# CNC-PowerSwitch-2016-v0_92.net
KiCad netlist of a schematic drawn in EAGLE
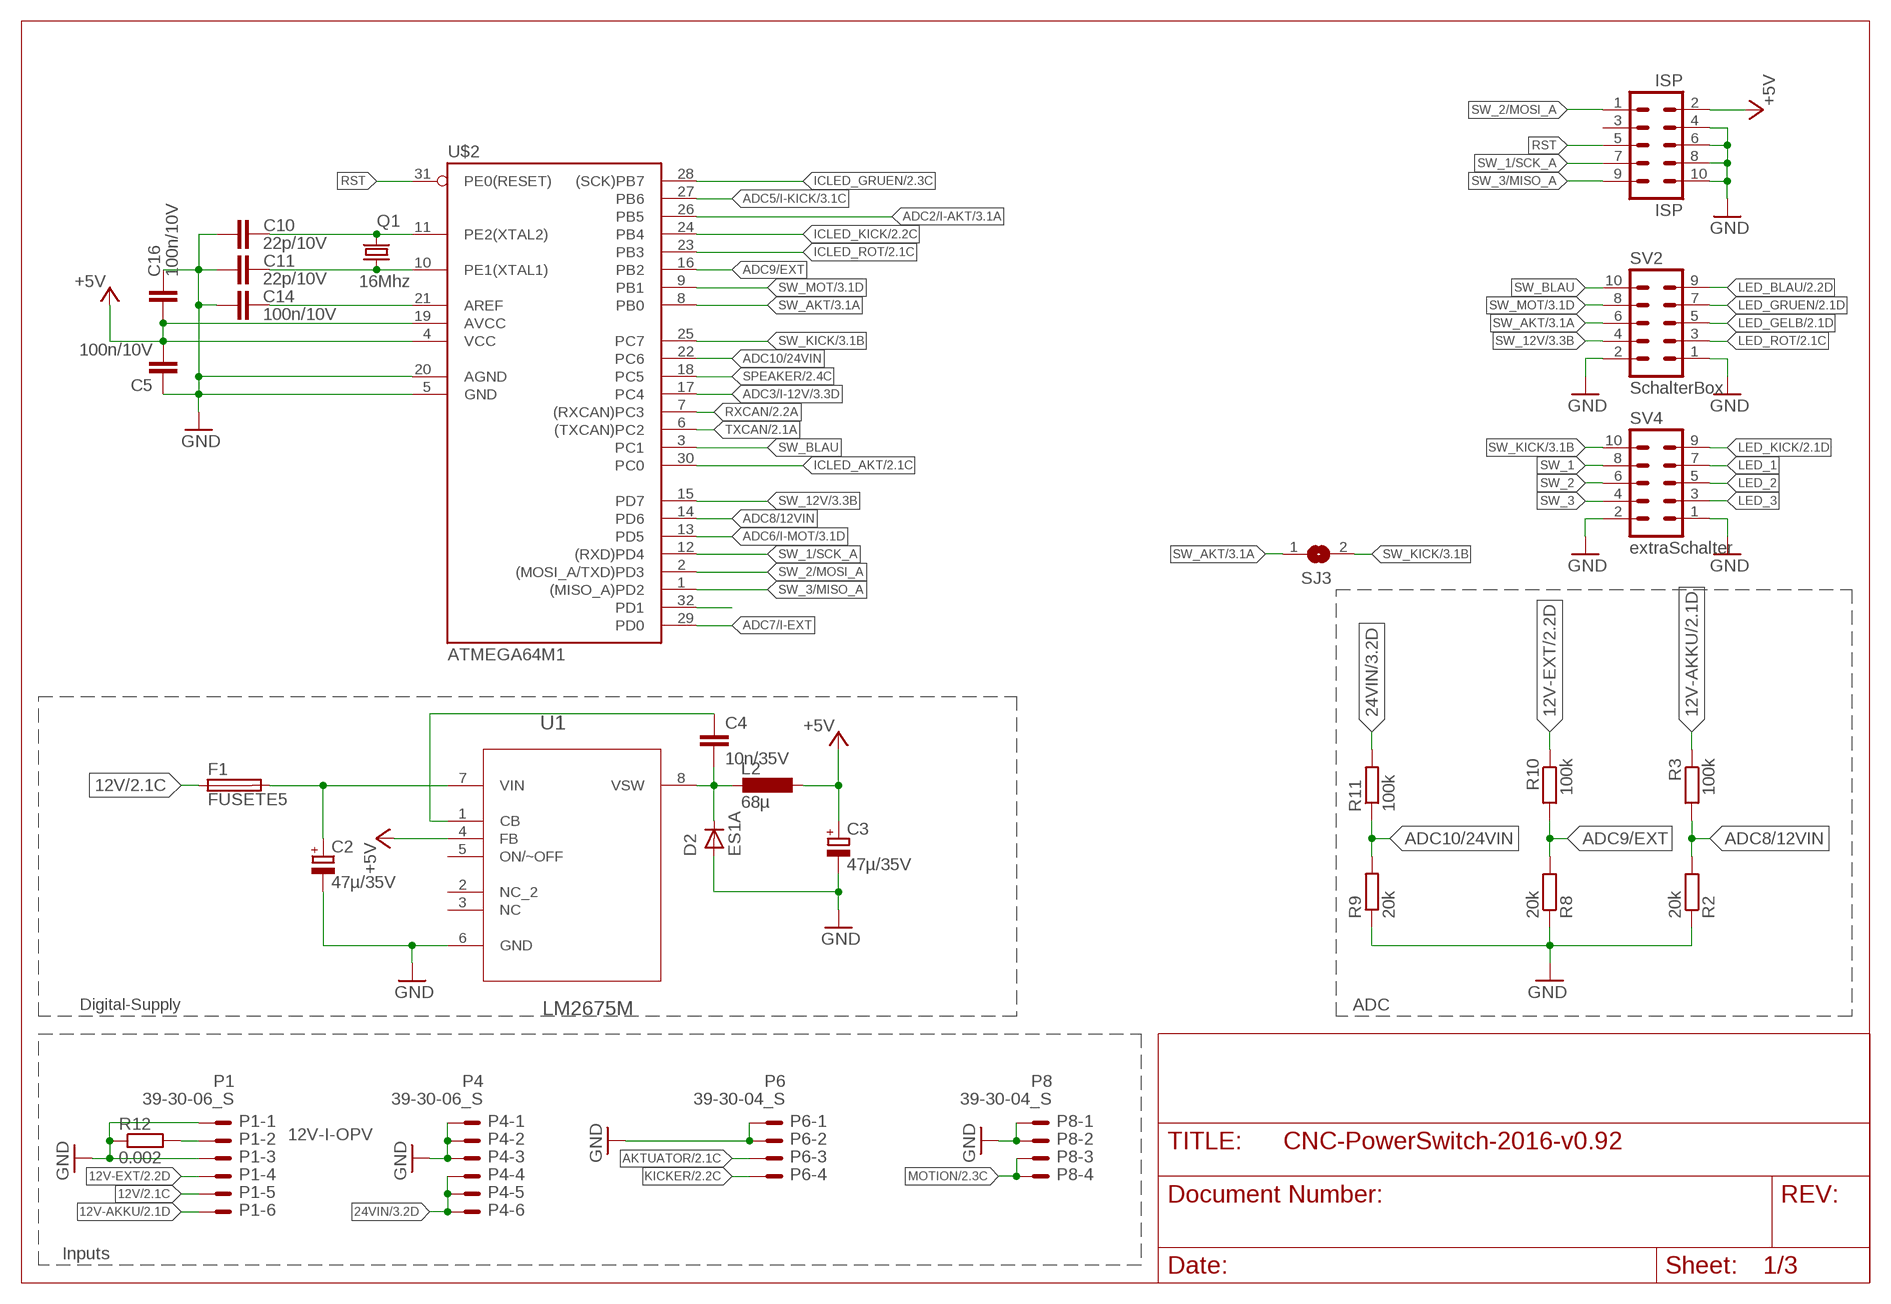
[diagram p0: schematic, sheet 1]
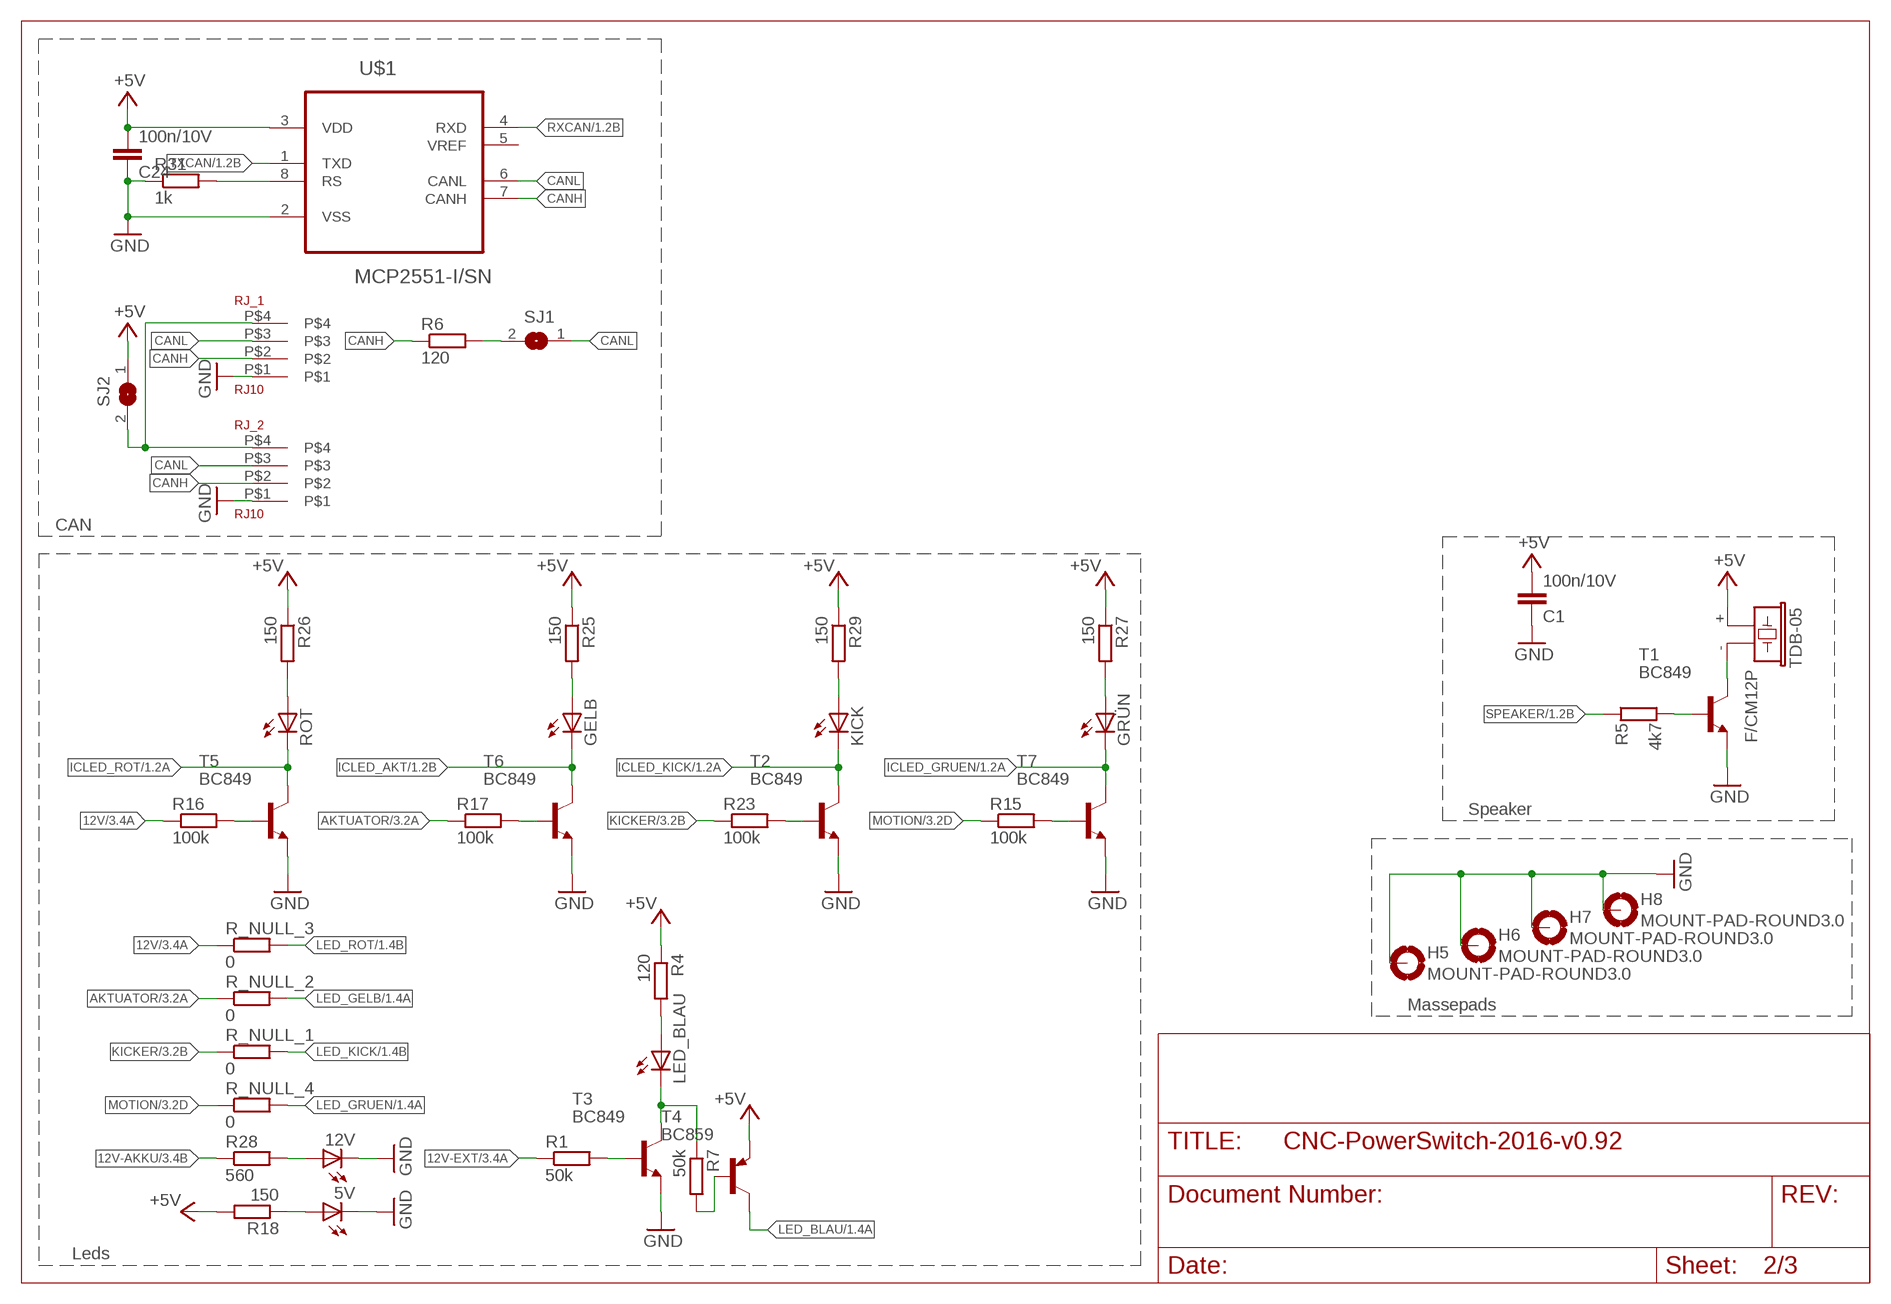
[diagram p1: schematic, sheet 2]
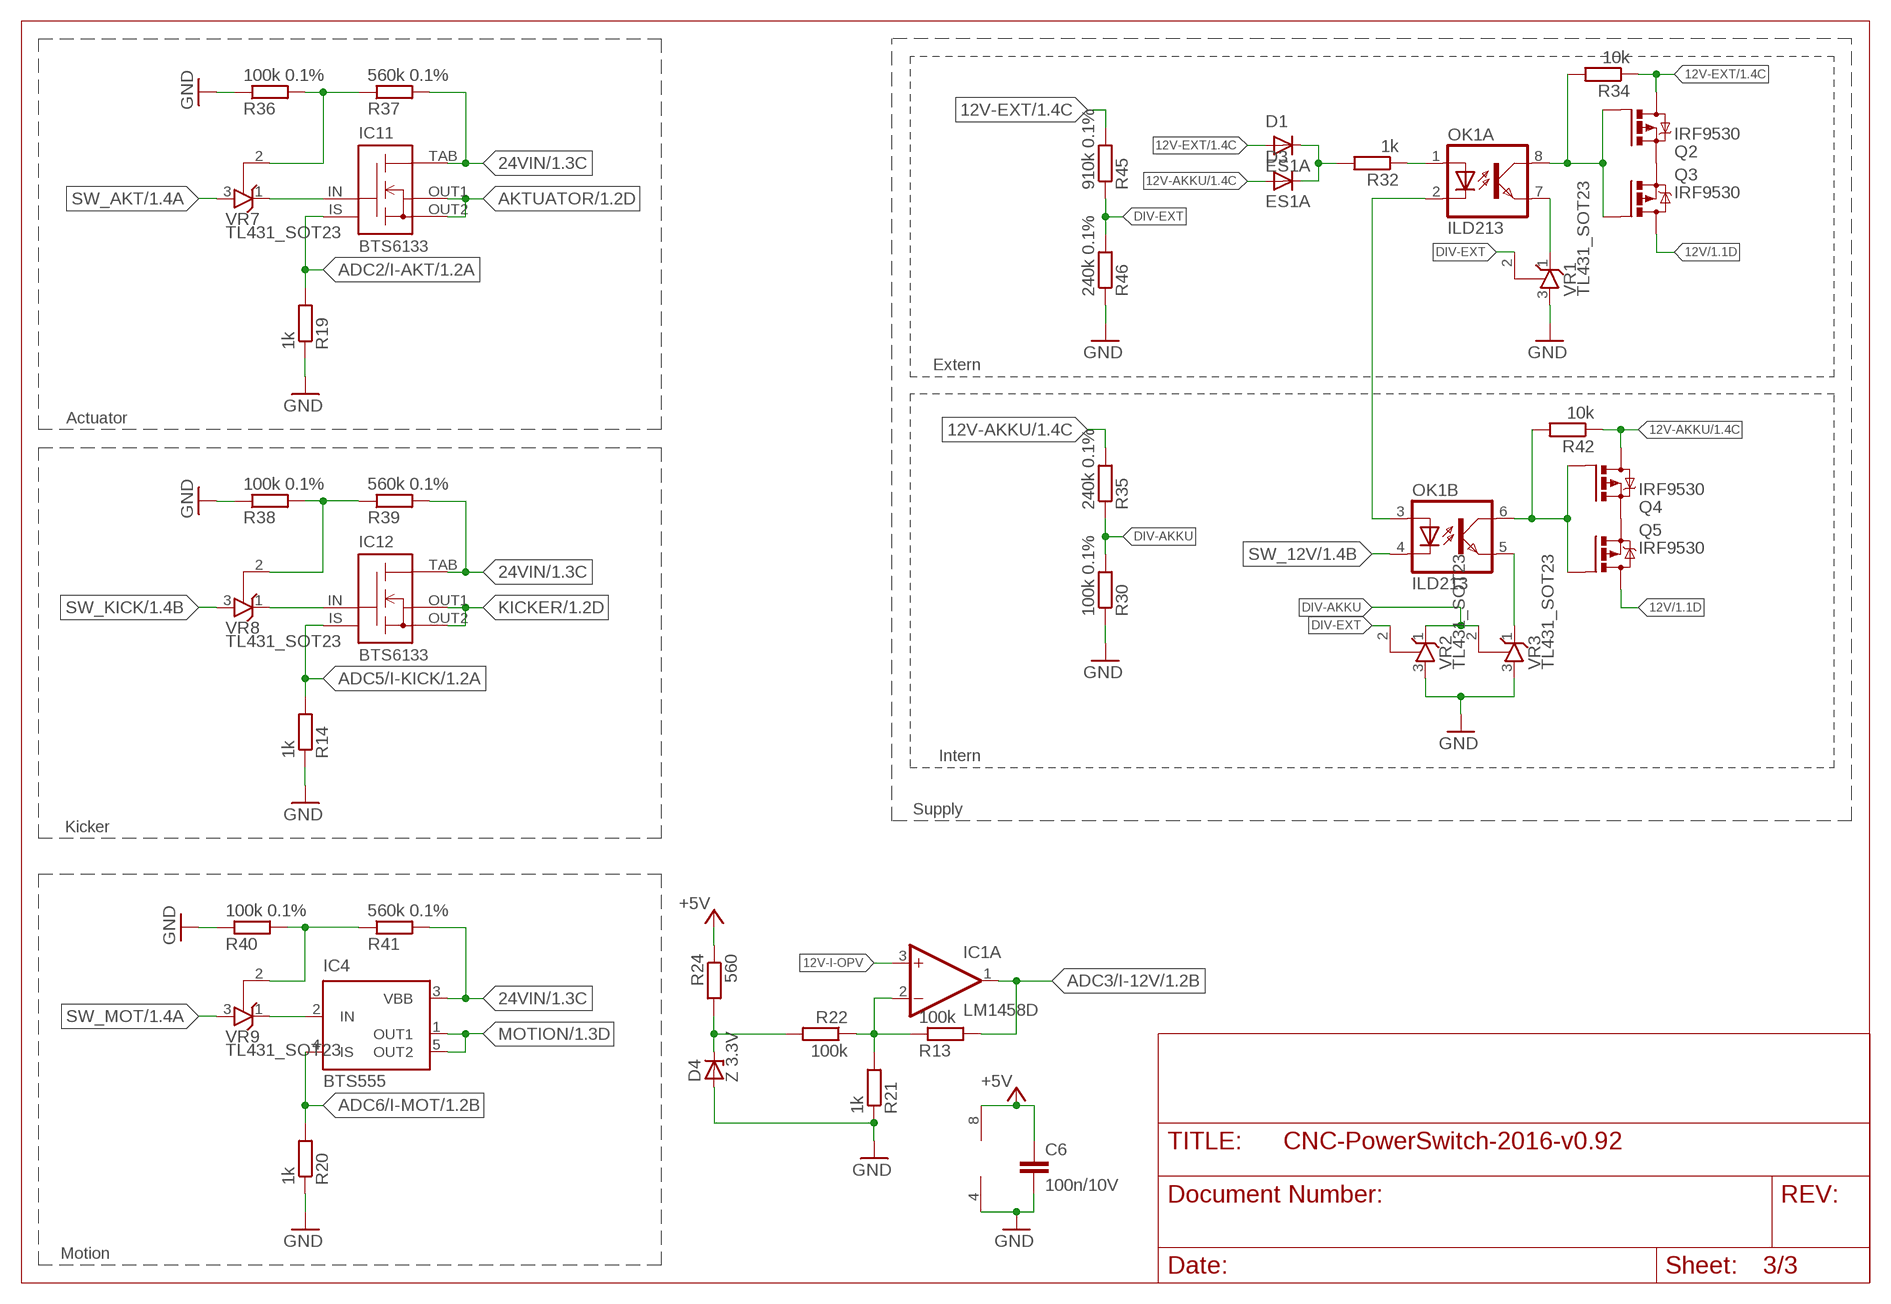
[diagram p2: schematic, sheet 3]

(export (version "E")
  (design (tool "Eeschema 10.0.6"))
  (components
    (comp (ref "C6")
      (value "100n/10V")
      (footprint "eagle-import:C0603")
      (libsource (lib "eagle-import") (part "C-EUC0603"))
    )
    (comp (ref "D1")
      (value "ES1A")
      (footprint "eagle-import:SMA-DO214AC")
      (libsource (lib "eagle-import") (part "GF1"))
    )
    (comp (ref "D3")
      (value "ES1A")
      (footprint "eagle-import:SMA-DO214AC")
      (libsource (lib "eagle-import") (part "GF1"))
    )
    (comp (ref "D4")
      (value "Z 3.3V")
      (footprint "eagle-import:SOT23")
      (libsource (lib "eagle-import") (part "ZENER-DIODESOT23"))
    )
    (comp (ref "IC1")
      (value "LM1458D")
      (footprint "eagle-import:SO08")
      (libsource (lib "eagle-import") (part "1458DLM"))
    )
    (comp (ref "IC4")
      (value "BTS555")
      (footprint "eagle-import:TO220-51")
      (fields (field (name "MF") "FARNELL") (field (name "MPN") "BTS555."))
      (libsource (lib "eagle-import") (part "BTS555"))
    )
    (comp (ref "IC11")
      (value "BTS6133")
      (footprint "eagle-import:TO252-51")
      (libsource (lib "eagle-import") (part "BTS6133"))
    )
    (comp (ref "IC12")
      (value "BTS6133")
      (footprint "eagle-import:TO252-51")
      (libsource (lib "eagle-import") (part "BTS6133"))
    )
    (comp (ref "OK1")
      (value "ILD213")
      (footprint "eagle-import:SOIC08")
      (fields (field (name "MF") "VISHAY/TELEFUNKEN") (field (name "MPN") "ILD213T"))
      (libsource (lib "eagle-import") (part "ILD213"))
    )
    (comp (ref "Q2")
      (value "IRF9530")
      (footprint "eagle-import:TO220BV")
      (libsource (lib "eagle-import") (part "IRF9530"))
    )
    (comp (ref "Q3")
      (value "IRF9530")
      (footprint "eagle-import:TO220BV")
      (libsource (lib "eagle-import") (part "IRF9530"))
    )
    (comp (ref "Q4")
      (value "IRF9530")
      (footprint "eagle-import:TO220BV")
      (libsource (lib "eagle-import") (part "IRF9530"))
    )
    (comp (ref "Q5")
      (value "IRF9530")
      (footprint "eagle-import:TO220BV")
      (libsource (lib "eagle-import") (part "IRF9530"))
    )
    (comp (ref "R13")
      (value "100k")
      (footprint "eagle-import:R0805")
      (libsource (lib "eagle-import") (part "R-EU_R0805"))
    )
    (comp (ref "R14")
      (value "1k")
      (footprint "eagle-import:R0805")
      (libsource (lib "eagle-import") (part "R-EU_R0805"))
    )
    (comp (ref "R19")
      (value "1k")
      (footprint "eagle-import:R0805")
      (libsource (lib "eagle-import") (part "R-EU_R0805"))
    )
    (comp (ref "R20")
      (value "1k")
      (footprint "eagle-import:R0805")
      (libsource (lib "eagle-import") (part "R-EU_R0805"))
    )
    (comp (ref "R21")
      (value "1k")
      (footprint "eagle-import:R0805")
      (libsource (lib "eagle-import") (part "R-EU_R0805"))
    )
    (comp (ref "R22")
      (value "100k")
      (footprint "eagle-import:R0805")
      (libsource (lib "eagle-import") (part "R-EU_R0805"))
    )
    (comp (ref "R24")
      (value "560")
      (footprint "eagle-import:R0805")
      (libsource (lib "eagle-import") (part "R-EU_R0805"))
    )
    (comp (ref "R30")
      (value "100k 0.1%")
      (footprint "eagle-import:R0805")
      (libsource (lib "eagle-import") (part "R-EU_R0805"))
    )
    (comp (ref "R32")
      (value "1k")
      (footprint "eagle-import:R0805")
      (libsource (lib "eagle-import") (part "R-EU_R0805"))
    )
    (comp (ref "R34")
      (value "10k")
      (footprint "eagle-import:R0805")
      (libsource (lib "eagle-import") (part "R-EU_R0805"))
    )
    (comp (ref "R35")
      (value "240k 0.1%")
      (footprint "eagle-import:R0805")
      (libsource (lib "eagle-import") (part "R-EU_R0805"))
    )
    (comp (ref "R36")
      (value "100k 0.1%")
      (footprint "eagle-import:R0805")
      (libsource (lib "eagle-import") (part "R-EU_R0805"))
    )
    (comp (ref "R37")
      (value "560k 0.1%")
      (footprint "eagle-import:R0805")
      (libsource (lib "eagle-import") (part "R-EU_R0805"))
    )
    (comp (ref "R38")
      (value "100k 0.1%")
      (footprint "eagle-import:R0805")
      (libsource (lib "eagle-import") (part "R-EU_R0805"))
    )
    (comp (ref "R39")
      (value "560k 0.1%")
      (footprint "eagle-import:R0805")
      (libsource (lib "eagle-import") (part "R-EU_R0805"))
    )
    (comp (ref "R40")
      (value "100k 0.1%")
      (footprint "eagle-import:R0805")
      (libsource (lib "eagle-import") (part "R-EU_R0805"))
    )
    (comp (ref "R41")
      (value "560k 0.1%")
      (footprint "eagle-import:R0805")
      (libsource (lib "eagle-import") (part "R-EU_R0805"))
    )
    (comp (ref "R42")
      (value "10k")
      (footprint "eagle-import:R0805")
      (libsource (lib "eagle-import") (part "R-EU_R0805"))
    )
    (comp (ref "R45")
      (value "910k 0.1%")
      (footprint "eagle-import:R0805")
      (libsource (lib "eagle-import") (part "R-EU_R0805"))
    )
    (comp (ref "R46")
      (value "240k 0.1%")
      (footprint "eagle-import:R0805")
      (libsource (lib "eagle-import") (part "R-EU_R0805"))
    )
    (comp (ref "VR1")
      (value "TL431_SOT23")
      (footprint "eagle-import:SOT23")
      (libsource (lib "eagle-import") (part "TL431_SOT23"))
    )
    (comp (ref "VR2")
      (value "TL431_SOT23")
      (footprint "eagle-import:SOT23")
      (libsource (lib "eagle-import") (part "TL431_SOT23"))
    )
    (comp (ref "VR3")
      (value "TL431_SOT23")
      (footprint "eagle-import:SOT23")
      (libsource (lib "eagle-import") (part "TL431_SOT23"))
    )
    (comp (ref "VR7")
      (value "TL431_SOT23")
      (footprint "eagle-import:SOT23")
      (libsource (lib "eagle-import") (part "TL431_SOT23"))
    )
    (comp (ref "VR8")
      (value "TL431_SOT23")
      (footprint "eagle-import:SOT23")
      (libsource (lib "eagle-import") (part "TL431_SOT23"))
    )
    (comp (ref "VR9")
      (value "TL431_SOT23")
      (footprint "eagle-import:SOT23")
      (libsource (lib "eagle-import") (part "TL431_SOT23"))
    )
    (comp (ref "C2")
      (value "47µ/35V")
      (footprint "eagle-import:PANASONIC_D")
      (libsource (lib "eagle-import") (part "CPOL-EUD"))
    )
    (comp (ref "C3")
      (value "47µ/35V")
      (footprint "eagle-import:PANASONIC_D")
      (libsource (lib "eagle-import") (part "CPOL-EUD"))
    )
    (comp (ref "C4")
      (value "10n/35V")
      (footprint "eagle-import:C0603")
      (libsource (lib "eagle-import") (part "C-EUC0603"))
    )
    (comp (ref "C5")
      (value "100n/10V")
      (footprint "eagle-import:C0603")
      (libsource (lib "eagle-import") (part "C-EUC0603"))
    )
    (comp (ref "C10")
      (value "22p/10V")
      (footprint "eagle-import:C0603")
      (libsource (lib "eagle-import") (part "C-EUC0603"))
    )
    (comp (ref "C11")
      (value "22p/10V")
      (footprint "eagle-import:C0603")
      (libsource (lib "eagle-import") (part "C-EUC0603"))
    )
    (comp (ref "C14")
      (value "100n/10V")
      (footprint "eagle-import:C0603")
      (libsource (lib "eagle-import") (part "C-EUC0603"))
    )
    (comp (ref "C16")
      (value "100n/10V")
      (footprint "eagle-import:C0603")
      (libsource (lib "eagle-import") (part "C-EUC0603"))
    )
    (comp (ref "D2")
      (value "ES1A")
      (footprint "eagle-import:SMA-DO214AC")
      (libsource (lib "eagle-import") (part "GF1"))
    )
    (comp (ref "F1")
      (value "FUSETE5")
      (footprint "eagle-import:TE5")
      (libsource (lib "eagle-import") (part "FUSETE5"))
    )
    (comp (ref "ISP")
      (value "ISP")
      (footprint "eagle-import:ML10")
      (libsource (lib "eagle-import") (part "ML10"))
    )
    (comp (ref "L2")
      (value "68µ")
      (footprint "eagle-import:PISM")
      (libsource (lib "eagle-import") (part "L-EUPISM"))
    )
    (comp (ref "P1")
      (value "39-30-06_S")
      (footprint "eagle-import:39-30-_06_")
      (libsource (lib "eagle-import") (part "39-30-?06?_S"))
    )
    (comp (ref "P4")
      (value "39-30-06_S")
      (footprint "eagle-import:39-30-_06_")
      (libsource (lib "eagle-import") (part "39-30-?06?_S"))
    )
    (comp (ref "P6")
      (value "39-30-04_S")
      (footprint "eagle-import:39-30-_04_")
      (libsource (lib "eagle-import") (part "39-30-?04?_S"))
    )
    (comp (ref "P8")
      (value "39-30-04_S")
      (footprint "eagle-import:39-30-_04_")
      (libsource (lib "eagle-import") (part "39-30-?04?_S"))
    )
    (comp (ref "Q1")
      (value "16Mhz")
      (footprint "eagle-import:HC49UP")
      (libsource (lib "eagle-import") (part "CRYSTALHC49UP"))
    )
    (comp (ref "R2")
      (value "20k")
      (footprint "eagle-import:R0805")
      (libsource (lib "eagle-import") (part "R-EU_R0805"))
    )
    (comp (ref "R3")
      (value "100k")
      (footprint "eagle-import:R0805")
      (libsource (lib "eagle-import") (part "R-EU_R0805"))
    )
    (comp (ref "R8")
      (value "20k")
      (footprint "eagle-import:R0805")
      (libsource (lib "eagle-import") (part "R-EU_R0805"))
    )
    (comp (ref "R9")
      (value "20k")
      (footprint "eagle-import:R0805")
      (libsource (lib "eagle-import") (part "R-EU_R0805"))
    )
    (comp (ref "R10")
      (value "100k")
      (footprint "eagle-import:R0805")
      (libsource (lib "eagle-import") (part "R-EU_R0805"))
    )
    (comp (ref "R11")
      (value "100k")
      (footprint "eagle-import:R0805")
      (libsource (lib "eagle-import") (part "R-EU_R0805"))
    )
    (comp (ref "R12")
      (value "0.002")
      (footprint "eagle-import:R2512")
      (libsource (lib "eagle-import") (part "R-EU_R2512"))
    )
    (comp (ref "SJ3") (value "SJ") (footprint "eagle-import:SJ") (libsource (lib "eagle-import") (part "SJ")))
    (comp (ref "SV2")
      (value "SchalterBox")
      (footprint "eagle-import:ML10")
      (libsource (lib "eagle-import") (part "ML10"))
    )
    (comp (ref "SV4")
      (value "extraSchalter")
      (footprint "eagle-import:ML10")
      (libsource (lib "eagle-import") (part "ML10"))
    )
    (comp (ref "U$2")
      (value "ATMEGA64M1")
      (footprint "eagle-import:TQFP32-08")
      (libsource (lib "eagle-import") (part "ATMEGA64M1"))
    )
    (comp (ref "U1")
      (value "LM2675M")
      (footprint "eagle-import:SOIC127P620X175-8N")
      (fields (field (name "MPN") "LM2675M-3.3"))
      (libsource (lib "eagle-import") (part "LM2675M-3.3"))
    )
    (comp (ref "5V")
      (value "LEDCHIPLED_0805")
      (footprint "eagle-import:CHIPLED_0805")
      (libsource (lib "eagle-import") (part "LEDCHIPLED_0805"))
    )
    (comp (ref "12V")
      (value "LEDCHIPLED_0805")
      (footprint "eagle-import:CHIPLED_0805")
      (libsource (lib "eagle-import") (part "LEDCHIPLED_0805"))
    )
    (comp (ref "C1")
      (value "100n/10V")
      (footprint "eagle-import:C0603")
      (libsource (lib "eagle-import") (part "C-EUC0603"))
    )
    (comp (ref "C24")
      (value "100n/10V")
      (footprint "eagle-import:C0603")
      (libsource (lib "eagle-import") (part "C-EUC0603"))
    )
    (comp (ref "GELB")
      (value "LEDCHIPLED_0805")
      (footprint "eagle-import:CHIPLED_0805")
      (libsource (lib "eagle-import") (part "LEDCHIPLED_0805"))
    )
    (comp (ref "GRÜN")
      (value "LEDCHIPLED_0805")
      (footprint "eagle-import:CHIPLED_0805")
      (libsource (lib "eagle-import") (part "LEDCHIPLED_0805"))
    )
    (comp (ref "H5")
      (value "MOUNT-PAD-ROUND3.0")
      (footprint "eagle-import:3,0-PAD")
      (libsource (lib "eagle-import") (part "MOUNT-PAD-ROUND3.0"))
    )
    (comp (ref "H6")
      (value "MOUNT-PAD-ROUND3.0")
      (footprint "eagle-import:3,0-PAD")
      (libsource (lib "eagle-import") (part "MOUNT-PAD-ROUND3.0"))
    )
    (comp (ref "H7")
      (value "MOUNT-PAD-ROUND3.0")
      (footprint "eagle-import:3,0-PAD")
      (libsource (lib "eagle-import") (part "MOUNT-PAD-ROUND3.0"))
    )
    (comp (ref "H8")
      (value "MOUNT-PAD-ROUND3.0")
      (footprint "eagle-import:3,0-PAD")
      (libsource (lib "eagle-import") (part "MOUNT-PAD-ROUND3.0"))
    )
    (comp (ref "KICK")
      (value "LEDCHIPLED_0805")
      (footprint "eagle-import:CHIPLED_0805")
      (libsource (lib "eagle-import") (part "LEDCHIPLED_0805"))
    )
    (comp (ref "LED_BLAU")
      (value "LEDCHIPLED_0805")
      (footprint "eagle-import:CHIPLED_0805")
      (libsource (lib "eagle-import") (part "LEDCHIPLED_0805"))
    )
    (comp (ref "R1")
      (value "50k")
      (footprint "eagle-import:R0805")
      (libsource (lib "eagle-import") (part "R-EU_R0805"))
    )
    (comp (ref "R4")
      (value "120")
      (footprint "eagle-import:R0805")
      (libsource (lib "eagle-import") (part "R-EU_R0805"))
    )
    (comp (ref "R5")
      (value "4k7")
      (footprint "eagle-import:R0805")
      (libsource (lib "eagle-import") (part "R-EU_R0805"))
    )
    (comp (ref "R6")
      (value "120")
      (footprint "eagle-import:M0805")
      (libsource (lib "eagle-import") (part "R-EU_M0805"))
    )
    (comp (ref "R7")
      (value "50k")
      (footprint "eagle-import:R0805")
      (libsource (lib "eagle-import") (part "R-EU_R0805"))
    )
    (comp (ref "R15")
      (value "100k")
      (footprint "eagle-import:R0805")
      (libsource (lib "eagle-import") (part "R-EU_R0805"))
    )
    (comp (ref "R16")
      (value "100k")
      (footprint "eagle-import:R0805")
      (libsource (lib "eagle-import") (part "R-EU_R0805"))
    )
    (comp (ref "R17")
      (value "100k")
      (footprint "eagle-import:R0805")
      (libsource (lib "eagle-import") (part "R-EU_R0805"))
    )
    (comp (ref "R18")
      (value "150")
      (footprint "eagle-import:R0805")
      (libsource (lib "eagle-import") (part "R-EU_R0805"))
    )
    (comp (ref "R23")
      (value "100k")
      (footprint "eagle-import:R0805")
      (libsource (lib "eagle-import") (part "R-EU_R0805"))
    )
    (comp (ref "R25")
      (value "150")
      (footprint "eagle-import:R0805")
      (libsource (lib "eagle-import") (part "R-EU_R0805"))
    )
    (comp (ref "R26")
      (value "150")
      (footprint "eagle-import:R0805")
      (libsource (lib "eagle-import") (part "R-EU_R0805"))
    )
    (comp (ref "R27")
      (value "150")
      (footprint "eagle-import:R0805")
      (libsource (lib "eagle-import") (part "R-EU_R0805"))
    )
    (comp (ref "R28")
      (value "560")
      (footprint "eagle-import:R0805")
      (libsource (lib "eagle-import") (part "R-EU_R0805"))
    )
    (comp (ref "R29")
      (value "150")
      (footprint "eagle-import:R0805")
      (libsource (lib "eagle-import") (part "R-EU_R0805"))
    )
    (comp (ref "R31")
      (value "1k")
      (footprint "eagle-import:R0805")
      (libsource (lib "eagle-import") (part "R-EU_R0805"))
    )
    (comp (ref "RJ_1")
      (value "RJ10")
      (footprint "eagle-import:RJ10")
      (libsource (lib "eagle-import") (part "RJ10"))
    )
    (comp (ref "RJ_2")
      (value "RJ10")
      (footprint "eagle-import:RJ10")
      (libsource (lib "eagle-import") (part "RJ10"))
    )
    (comp (ref "ROT")
      (value "LEDCHIPLED_0805")
      (footprint "eagle-import:CHIPLED_0805")
      (libsource (lib "eagle-import") (part "LEDCHIPLED_0805"))
    )
    (comp (ref "R_NULL_1")
      (value "0")
      (footprint "eagle-import:R0402")
      (libsource (lib "eagle-import") (part "R-EU_R0402"))
    )
    (comp (ref "R_NULL_2")
      (value "0")
      (footprint "eagle-import:R0402")
      (libsource (lib "eagle-import") (part "R-EU_R0402"))
    )
    (comp (ref "R_NULL_3")
      (value "0")
      (footprint "eagle-import:R0402")
      (libsource (lib "eagle-import") (part "R-EU_R0402"))
    )
    (comp (ref "R_NULL_4")
      (value "0")
      (footprint "eagle-import:R0402")
      (libsource (lib "eagle-import") (part "R-EU_R0402"))
    )
    (comp (ref "SJ1") (value "SJ") (footprint "eagle-import:SJ") (libsource (lib "eagle-import") (part "SJ")))
    (comp (ref "SJ2") (value "SJ") (footprint "eagle-import:SJ") (libsource (lib "eagle-import") (part "SJ")))
    (comp (ref "T1")
      (value "BC849")
      (footprint "eagle-import:SOT23")
      (libsource (lib "eagle-import") (part "BC849"))
    )
    (comp (ref "T2")
      (value "BC849")
      (footprint "eagle-import:SOT23")
      (libsource (lib "eagle-import") (part "BC849"))
    )
    (comp (ref "T3")
      (value "BC849")
      (footprint "eagle-import:SOT23")
      (libsource (lib "eagle-import") (part "BC849"))
    )
    (comp (ref "T4")
      (value "BC859")
      (footprint "eagle-import:SOT23-BEC")
      (libsource (lib "eagle-import") (part "-PNP-SOT23-BECBC858C"))
    )
    (comp (ref "T5")
      (value "BC849")
      (footprint "eagle-import:SOT23")
      (libsource (lib "eagle-import") (part "BC849"))
    )
    (comp (ref "T6")
      (value "BC849")
      (footprint "eagle-import:SOT23")
      (libsource (lib "eagle-import") (part "BC849"))
    )
    (comp (ref "T7")
      (value "BC849")
      (footprint "eagle-import:SOT23")
      (libsource (lib "eagle-import") (part "BC849"))
    )
    (comp (ref "TDB-05")
      (value "F/CM12P")
      (footprint "eagle-import:F_CM12P")
      (libsource (lib "eagle-import") (part "F/CM12P"))
    )
    (comp (ref "U$1")
      (value "MCP2551-I/SN")
      (footprint "eagle-import:SOIC127P600X175-8N")
      (libsource (lib "eagle-import") (part "MCP2551-I/SN"))
    )
  )
  (nets
    (net (code "1") (name "+5V") (class "Default")
      (node (ref "C1") (pin "2") (pinfunction "2_2") (pintype "passive"))
      (node (ref "C16") (pin "1") (pinfunction "1_1") (pintype "passive"))
      (node (ref "C24") (pin "2") (pinfunction "2_2") (pintype "passive"))
      (node (ref "C3") (pin "+") (pinfunction "+_+") (pintype "passive"))
      (node (ref "C5") (pin "2") (pinfunction "2_2") (pintype "passive"))
      (node (ref "C6") (pin "1") (pinfunction "1_1") (pintype "passive"))
      (node (ref "IC1") (pin "8") (pinfunction "V+_8") (pintype "power_in"))
      (node (ref "ISP") (pin "2") (pinfunction "2_2") (pintype "passive"))
      (node (ref "L2") (pin "1") (pinfunction "1_1") (pintype "passive"))
      (node (ref "R18") (pin "2") (pinfunction "2_2") (pintype "passive"))
      (node (ref "R24") (pin "1") (pinfunction "1_1") (pintype "passive"))
      (node (ref "R25") (pin "1") (pinfunction "1_1") (pintype "passive"))
      (node (ref "R26") (pin "1") (pinfunction "1_1") (pintype "passive"))
      (node (ref "R27") (pin "1") (pinfunction "1_1") (pintype "passive"))
      (node (ref "R29") (pin "1") (pinfunction "1_1") (pintype "passive"))
      (node (ref "R4") (pin "1") (pinfunction "1_1") (pintype "passive"))
      (node (ref "SJ2") (pin "1") (pinfunction "1_1") (pintype "passive"))
      (node (ref "T4") (pin "E") (pinfunction "E_E") (pintype "passive"))
      (node (ref "TDB-05") (pin "+") (pinfunction "1_+") (pintype "passive"))
      (node (ref "U$1") (pin "3") (pinfunction "VDD_3") (pintype "power_in"))
      (node (ref "U$2") (pin "19") (pinfunction "AVCC_19") (pintype "bidirectional"))
      (node (ref "U$2") (pin "4") (pinfunction "VCC_4") (pintype "bidirectional"))
      (node (ref "U1") (pin "4") (pinfunction "FB_4") (pintype "input"))
    )
    (net (code "2") (name "12V") (class "Default")
      (node (ref "F1") (pin "1") (pinfunction "1_1") (pintype "passive"))
      (node (ref "P1") (pin "5") (pinfunction "P_5") (pintype "passive"))
      (node (ref "Q3") (pin "D") (pinfunction "D_D") (pintype "passive"))
      (node (ref "Q5") (pin "D") (pinfunction "D_D") (pintype "passive"))
      (node (ref "R16") (pin "1") (pinfunction "1_1") (pintype "passive"))
      (node (ref "R_NULL_3") (pin "1") (pinfunction "1_1") (pintype "passive"))
    )
    (net (code "3") (name "12V-AKKU") (class "Default")
      (node (ref "D3") (pin "A") (pinfunction "A_A") (pintype "passive"))
      (node (ref "P1") (pin "6") (pinfunction "P_6") (pintype "passive"))
      (node (ref "Q4") (pin "D") (pinfunction "D_D") (pintype "passive"))
      (node (ref "R28") (pin "1") (pinfunction "1_1") (pintype "passive"))
      (node (ref "R3") (pin "1") (pinfunction "1_1") (pintype "passive"))
      (node (ref "R35") (pin "2") (pinfunction "2_2") (pintype "passive"))
      (node (ref "R42") (pin "1") (pinfunction "1_1") (pintype "passive"))
    )
    (net (code "4") (name "12V-EXT") (class "Default")
      (node (ref "D1") (pin "A") (pinfunction "A_A") (pintype "passive"))
      (node (ref "P1") (pin "4") (pinfunction "P_4") (pintype "passive"))
      (node (ref "Q2") (pin "D") (pinfunction "D_D") (pintype "passive"))
      (node (ref "R1") (pin "1") (pinfunction "1_1") (pintype "passive"))
      (node (ref "R10") (pin "1") (pinfunction "1_1") (pintype "passive"))
      (node (ref "R34") (pin "1") (pinfunction "1_1") (pintype "passive"))
      (node (ref "R45") (pin "2") (pinfunction "2_2") (pintype "passive"))
    )
    (net (code "5") (name "12V-I-OPV") (class "Default")
      (node (ref "IC1") (pin "3") (pinfunction "+IN_3") (pintype "input"))
      (node (ref "P1") (pin "2") (pinfunction "P_2") (pintype "passive"))
      (node (ref "R12") (pin "2") (pinfunction "2_2") (pintype "passive"))
    )
    (net (code "6") (name "24VIN") (class "Default")
      (node (ref "IC11") (pin "TAB") (pinfunction "VBB_TAB") (pintype "power_in"))
      (node (ref "IC12") (pin "TAB") (pinfunction "VBB_TAB") (pintype "power_in"))
      (node (ref "IC4") (pin "3") (pinfunction "VBB_3") (pintype "passive"))
      (node (ref "P4") (pin "4") (pinfunction "P_4") (pintype "passive"))
      (node (ref "P4") (pin "5") (pinfunction "P_5") (pintype "passive"))
      (node (ref "P4") (pin "6") (pinfunction "P_6") (pintype "passive"))
      (node (ref "R11") (pin "2") (pinfunction "2_2") (pintype "passive"))
      (node (ref "R37") (pin "2") (pinfunction "2_2") (pintype "passive"))
      (node (ref "R39") (pin "2") (pinfunction "2_2") (pintype "passive"))
      (node (ref "R41") (pin "2") (pinfunction "2_2") (pintype "passive"))
    )
    (net (code "7") (name "ADC2{slash}I-AKT") (class "Default")
      (node (ref "IC11") (pin "IS") (pinfunction "IS_IS") (pintype "passive"))
      (node (ref "R19") (pin "2") (pinfunction "2_2") (pintype "passive"))
      (node (ref "U$2") (pin "26") (pinfunction "PB5_26") (pintype "bidirectional"))
    )
    (net (code "8") (name "ADC3{slash}I-12V") (class "Default")
      (node (ref "IC1") (pin "1") (pinfunction "OUT_1") (pintype "output"))
      (node (ref "R13") (pin "2") (pinfunction "2_2") (pintype "passive"))
      (node (ref "U$2") (pin "17") (pinfunction "PC4_17") (pintype "bidirectional"))
    )
    (net (code "9") (name "ADC5{slash}I-KICK") (class "Default")
      (node (ref "IC12") (pin "IS") (pinfunction "IS_IS") (pintype "passive"))
      (node (ref "R14") (pin "2") (pinfunction "2_2") (pintype "passive"))
      (node (ref "U$2") (pin "27") (pinfunction "PB6_27") (pintype "bidirectional"))
    )
    (net (code "10") (name "ADC6{slash}I-MOT") (class "Default")
      (node (ref "IC4") (pin "4") (pinfunction "IS_4") (pintype "passive"))
      (node (ref "R20") (pin "2") (pinfunction "2_2") (pintype "passive"))
      (node (ref "U$2") (pin "13") (pinfunction "PD5_13") (pintype "bidirectional"))
    )
    (net (code "11") (name "ADC7{slash}I-EXT") (class "Default")
      (node (ref "U$2") (pin "29") (pinfunction "PD0_29") (pintype "bidirectional"))
    )
    (net (code "12") (name "ADC8{slash}12VIN") (class "Default")
      (node (ref "R2") (pin "2") (pinfunction "2_2") (pintype "passive"))
      (node (ref "R3") (pin "2") (pinfunction "2_2") (pintype "passive"))
      (node (ref "U$2") (pin "14") (pinfunction "PD6_14") (pintype "bidirectional"))
    )
    (net (code "13") (name "ADC9{slash}EXT") (class "Default")
      (node (ref "R10") (pin "2") (pinfunction "2_2") (pintype "passive"))
      (node (ref "R8") (pin "2") (pinfunction "2_2") (pintype "passive"))
      (node (ref "U$2") (pin "16") (pinfunction "PB2_16") (pintype "bidirectional"))
    )
    (net (code "14") (name "ADC10{slash}24VIN") (class "Default")
      (node (ref "R11") (pin "1") (pinfunction "1_1") (pintype "passive"))
      (node (ref "R9") (pin "2") (pinfunction "2_2") (pintype "passive"))
      (node (ref "U$2") (pin "22") (pinfunction "PC6_22") (pintype "bidirectional"))
    )
    (net (code "15") (name "AKTUATOR") (class "Default")
      (node (ref "IC11") (pin "OUT1") (pinfunction "OUT_OUT1") (pintype "passive"))
      (node (ref "IC11") (pin "OUT2") (pinfunction "OUT_OUT2") (pintype "passive"))
      (node (ref "P6") (pin "3") (pinfunction "P_3") (pintype "passive"))
      (node (ref "R17") (pin "1") (pinfunction "1_1") (pintype "passive"))
      (node (ref "R_NULL_2") (pin "1") (pinfunction "1_1") (pintype "passive"))
    )
    (net (code "16") (name "CANH") (class "Default")
      (node (ref "R6") (pin "1") (pinfunction "1_1") (pintype "passive"))
      (node (ref "RJ_1") (pin "P$2") (pinfunction "P$2_P$2") (pintype "bidirectional"))
      (node (ref "RJ_2") (pin "P$2") (pinfunction "P$2_P$2") (pintype "bidirectional"))
      (node (ref "U$1") (pin "7") (pinfunction "CANH_7") (pintype "bidirectional"))
    )
    (net (code "17") (name "CANL") (class "Default")
      (node (ref "RJ_1") (pin "P$3") (pinfunction "P$3_P$3") (pintype "bidirectional"))
      (node (ref "RJ_2") (pin "P$3") (pinfunction "P$3_P$3") (pintype "bidirectional"))
      (node (ref "SJ1") (pin "1") (pinfunction "1_1") (pintype "passive"))
      (node (ref "U$1") (pin "6") (pinfunction "CANL_6") (pintype "bidirectional"))
    )
    (net (code "18") (name "DIV-AKKU") (class "Default")
      (node (ref "R30") (pin "2") (pinfunction "2_2") (pintype "passive"))
      (node (ref "R35") (pin "1") (pinfunction "1_1") (pintype "passive"))
      (node (ref "VR2") (pin "1") (pinfunction "C_1") (pintype "passive"))
      (node (ref "VR3") (pin "2") (pinfunction "R_2") (pintype "passive"))
    )
    (net (code "19") (name "DIV-EXT") (class "Default")
      (node (ref "R45") (pin "1") (pinfunction "1_1") (pintype "passive"))
      (node (ref "R46") (pin "2") (pinfunction "2_2") (pintype "passive"))
      (node (ref "VR1") (pin "2") (pinfunction "R_2") (pintype "passive"))
      (node (ref "VR2") (pin "2") (pinfunction "R_2") (pintype "passive"))
    )
    (net (code "20") (name "GND") (class "Default")
      (node (ref "12V") (pin "C") (pinfunction "C_C") (pintype "passive"))
      (node (ref "5V") (pin "C") (pinfunction "C_C") (pintype "passive"))
      (node (ref "C1") (pin "1") (pinfunction "1_1") (pintype "passive"))
      (node (ref "C10") (pin "1") (pinfunction "1_1") (pintype "passive"))
      (node (ref "C11") (pin "1") (pinfunction "1_1") (pintype "passive"))
      (node (ref "C14") (pin "1") (pinfunction "1_1") (pintype "passive"))
      (node (ref "C16") (pin "2") (pinfunction "2_2") (pintype "passive"))
      (node (ref "C2") (pin "-") (pinfunction "-_-") (pintype "passive"))
      (node (ref "C24") (pin "1") (pinfunction "1_1") (pintype "passive"))
      (node (ref "C3") (pin "-") (pinfunction "-_-") (pintype "passive"))
      (node (ref "C5") (pin "1") (pinfunction "1_1") (pintype "passive"))
      (node (ref "C6") (pin "2") (pinfunction "2_2") (pintype "passive"))
      (node (ref "D2") (pin "A") (pinfunction "A_A") (pintype "passive"))
      (node (ref "D4") (pin "1") (pinfunction "A_1") (pintype "passive"))
      (node (ref "H5") (pin "B3,0") (pinfunction "MOUNT_B3,0") (pintype "passive"))
      (node (ref "H6") (pin "B3,0") (pinfunction "MOUNT_B3,0") (pintype "passive"))
      (node (ref "H7") (pin "B3,0") (pinfunction "MOUNT_B3,0") (pintype "passive"))
      (node (ref "H8") (pin "B3,0") (pinfunction "MOUNT_B3,0") (pintype "passive"))
      (node (ref "IC1") (pin "4") (pinfunction "V-_4") (pintype "power_in"))
      (node (ref "ISP") (pin "10") (pinfunction "10_10") (pintype "passive"))
      (node (ref "ISP") (pin "4") (pinfunction "4_4") (pintype "passive"))
      (node (ref "ISP") (pin "6") (pinfunction "6_6") (pintype "passive"))
      (node (ref "ISP") (pin "8") (pinfunction "8_8") (pintype "passive"))
      (node (ref "P1") (pin "1") (pinfunction "P_1") (pintype "passive"))
      (node (ref "P1") (pin "3") (pinfunction "P_3") (pintype "passive"))
      (node (ref "P4") (pin "1") (pinfunction "P_1") (pintype "passive"))
      (node (ref "P4") (pin "2") (pinfunction "P_2") (pintype "passive"))
      (node (ref "P4") (pin "3") (pinfunction "P_3") (pintype "passive"))
      (node (ref "P6") (pin "1") (pinfunction "P_1") (pintype "passive"))
      (node (ref "P6") (pin "2") (pinfunction "P_2") (pintype "passive"))
      (node (ref "P8") (pin "1") (pinfunction "P_1") (pintype "passive"))
      (node (ref "P8") (pin "2") (pinfunction "P_2") (pintype "passive"))
      (node (ref "R12") (pin "1") (pinfunction "1_1") (pintype "passive"))
      (node (ref "R14") (pin "1") (pinfunction "1_1") (pintype "passive"))
      (node (ref "R19") (pin "1") (pinfunction "1_1") (pintype "passive"))
      (node (ref "R2") (pin "1") (pinfunction "1_1") (pintype "passive"))
      (node (ref "R20") (pin "1") (pinfunction "1_1") (pintype "passive"))
      (node (ref "R21") (pin "1") (pinfunction "1_1") (pintype "passive"))
      (node (ref "R30") (pin "1") (pinfunction "1_1") (pintype "passive"))
      (node (ref "R31") (pin "1") (pinfunction "1_1") (pintype "passive"))
      (node (ref "R36") (pin "1") (pinfunction "1_1") (pintype "passive"))
      (node (ref "R38") (pin "1") (pinfunction "1_1") (pintype "passive"))
      (node (ref "R40") (pin "1") (pinfunction "1_1") (pintype "passive"))
      (node (ref "R46") (pin "1") (pinfunction "1_1") (pintype "passive"))
      (node (ref "R8") (pin "1") (pinfunction "1_1") (pintype "passive"))
      (node (ref "R9") (pin "1") (pinfunction "1_1") (pintype "passive"))
      (node (ref "RJ_1") (pin "P$1") (pinfunction "P$1_P$1") (pintype "bidirectional"))
      (node (ref "RJ_2") (pin "P$1") (pinfunction "P$1_P$1") (pintype "bidirectional"))
      (node (ref "SV2") (pin "1") (pinfunction "1_1") (pintype "passive"))
      (node (ref "SV2") (pin "2") (pinfunction "2_2") (pintype "passive"))
      (node (ref "SV4") (pin "1") (pinfunction "1_1") (pintype "passive"))
      (node (ref "SV4") (pin "2") (pinfunction "2_2") (pintype "passive"))
      (node (ref "T1") (pin "2") (pinfunction "E_2") (pintype "passive"))
      (node (ref "T2") (pin "2") (pinfunction "E_2") (pintype "passive"))
      (node (ref "T3") (pin "2") (pinfunction "E_2") (pintype "passive"))
      (node (ref "T5") (pin "2") (pinfunction "E_2") (pintype "passive"))
      (node (ref "T6") (pin "2") (pinfunction "E_2") (pintype "passive"))
      (node (ref "T7") (pin "2") (pinfunction "E_2") (pintype "passive"))
      (node (ref "U$1") (pin "2") (pinfunction "VSS_2") (pintype "passive"))
      (node (ref "U$2") (pin "20") (pinfunction "AGND_20") (pintype "power_in"))
      (node (ref "U$2") (pin "5") (pinfunction "GND_5") (pintype "power_in"))
      (node (ref "U1") (pin "6") (pinfunction "GND_6") (pintype "passive"))
      (node (ref "VR1") (pin "3") (pinfunction "A_3") (pintype "passive"))
      (node (ref "VR2") (pin "3") (pinfunction "A_3") (pintype "passive"))
      (node (ref "VR3") (pin "3") (pinfunction "A_3") (pintype "passive"))
    )
    (net (code "21") (name "ICLED_AKT") (class "Default")
      (node (ref "GELB") (pin "C") (pinfunction "C_C") (pintype "passive"))
      (node (ref "T6") (pin "3") (pinfunction "C_3") (pintype "passive"))
      (node (ref "U$2") (pin "30") (pinfunction "PC0_30") (pintype "bidirectional"))
    )
    (net (code "22") (name "ICLED_GRUEN") (class "Default")
      (node (ref "GRÜN") (pin "C") (pinfunction "C_C") (pintype "passive"))
      (node (ref "T7") (pin "3") (pinfunction "C_3") (pintype "passive"))
      (node (ref "U$2") (pin "28") (pinfunction "(SCK)PB7_28") (pintype "bidirectional"))
    )
    (net (code "23") (name "ICLED_KICK") (class "Default")
      (node (ref "KICK") (pin "C") (pinfunction "C_C") (pintype "passive"))
      (node (ref "T2") (pin "3") (pinfunction "C_3") (pintype "passive"))
      (node (ref "U$2") (pin "24") (pinfunction "PB4_24") (pintype "bidirectional"))
    )
    (net (code "24") (name "ICLED_ROT") (class "Default")
      (node (ref "ROT") (pin "C") (pinfunction "C_C") (pintype "passive"))
      (node (ref "T5") (pin "3") (pinfunction "C_3") (pintype "passive"))
      (node (ref "U$2") (pin "23") (pinfunction "PB3_23") (pintype "bidirectional"))
    )
    (net (code "25") (name "KICKER") (class "Default")
      (node (ref "IC12") (pin "OUT1") (pinfunction "OUT_OUT1") (pintype "passive"))
      (node (ref "IC12") (pin "OUT2") (pinfunction "OUT_OUT2") (pintype "passive"))
      (node (ref "P6") (pin "4") (pinfunction "P_4") (pintype "passive"))
      (node (ref "R23") (pin "1") (pinfunction "1_1") (pintype "passive"))
      (node (ref "R_NULL_1") (pin "1") (pinfunction "1_1") (pintype "passive"))
    )
    (net (code "26") (name "LED_1") (class "Default")
      (node (ref "SV4") (pin "7") (pinfunction "7_7") (pintype "passive"))
    )
    (net (code "27") (name "LED_2") (class "Default")
      (node (ref "SV4") (pin "5") (pinfunction "5_5") (pintype "passive"))
    )
    (net (code "28") (name "LED_3") (class "Default")
      (node (ref "SV4") (pin "3") (pinfunction "3_3") (pintype "passive"))
    )
    (net (code "29") (name "LED_BLAU") (class "Default")
      (node (ref "SV2") (pin "9") (pinfunction "9_9") (pintype "passive"))
      (node (ref "T4") (pin "C") (pinfunction "C_C") (pintype "passive"))
    )
    (net (code "30") (name "LED_GELB") (class "Default")
      (node (ref "R_NULL_2") (pin "2") (pinfunction "2_2") (pintype "passive"))
      (node (ref "SV2") (pin "5") (pinfunction "5_5") (pintype "passive"))
    )
    (net (code "31") (name "LED_GRUEN") (class "Default")
      (node (ref "R_NULL_4") (pin "2") (pinfunction "2_2") (pintype "passive"))
      (node (ref "SV2") (pin "7") (pinfunction "7_7") (pintype "passive"))
    )
    (net (code "32") (name "LED_KICK") (class "Default")
      (node (ref "R_NULL_1") (pin "2") (pinfunction "2_2") (pintype "passive"))
      (node (ref "SV4") (pin "9") (pinfunction "9_9") (pintype "passive"))
    )
    (net (code "33") (name "LED_ROT") (class "Default")
      (node (ref "R_NULL_3") (pin "2") (pinfunction "2_2") (pintype "passive"))
      (node (ref "SV2") (pin "3") (pinfunction "3_3") (pintype "passive"))
    )
    (net (code "34") (name "MOTION") (class "Default")
      (node (ref "IC4") (pin "1") (pinfunction "OUT1_1") (pintype "passive"))
      (node (ref "IC4") (pin "5") (pinfunction "OUT2_5") (pintype "passive"))
      (node (ref "P8") (pin "3") (pinfunction "P_3") (pintype "passive"))
      (node (ref "P8") (pin "4") (pinfunction "P_4") (pintype "passive"))
      (node (ref "R15") (pin "1") (pinfunction "1_1") (pintype "passive"))
      (node (ref "R_NULL_4") (pin "1") (pinfunction "1_1") (pintype "passive"))
    )
    (net (code "35") (name "Net-(5V-PadA)") (class "Default")
      (node (ref "5V") (pin "A") (pinfunction "A_A") (pintype "passive"))
      (node (ref "R18") (pin "1") (pinfunction "1_1") (pintype "passive"))
    )
    (net (code "36") (name "Net-(12V-PadA)") (class "Default")
      (node (ref "12V") (pin "A") (pinfunction "A_A") (pintype "passive"))
      (node (ref "R28") (pin "2") (pinfunction "2_2") (pintype "passive"))
    )
    (net (code "37") (name "Net-(D1-C)") (class "Default")
      (node (ref "D1") (pin "K") (pinfunction "C_K") (pintype "passive"))
      (node (ref "D3") (pin "K") (pinfunction "C_K") (pintype "passive"))
      (node (ref "R32") (pin "2") (pinfunction "2_2") (pintype "passive"))
    )
    (net (code "38") (name "Net-(D2-C)") (class "Default")
      (node (ref "C4") (pin "2") (pinfunction "2_2") (pintype "passive"))
      (node (ref "D2") (pin "K") (pinfunction "C_K") (pintype "passive"))
      (node (ref "L2") (pin "2") (pinfunction "2_2") (pintype "passive"))
      (node (ref "U1") (pin "8") (pinfunction "VSW_8") (pintype "output"))
    )
    (net (code "39") (name "Net-(D4-C)") (class "Default")
      (node (ref "D4") (pin "3") (pinfunction "C_3") (pintype "passive"))
      (node (ref "R22") (pin "2") (pinfunction "2_2") (pintype "passive"))
      (node (ref "R24") (pin "2") (pinfunction "2_2") (pintype "passive"))
    )
    (net (code "40") (name "Net-(GELB-PadA)") (class "Default")
      (node (ref "GELB") (pin "A") (pinfunction "A_A") (pintype "passive"))
      (node (ref "R25") (pin "2") (pinfunction "2_2") (pintype "passive"))
    )
    (net (code "41") (name "Net-(GRÜN-PadA)") (class "Default")
      (node (ref "GRÜN") (pin "A") (pinfunction "A_A") (pintype "passive"))
      (node (ref "R27") (pin "2") (pinfunction "2_2") (pintype "passive"))
    )
    (net (code "42") (name "Net-(IC1A--IN)") (class "Default")
      (node (ref "IC1") (pin "2") (pinfunction "-IN_2") (pintype "input"))
      (node (ref "R13") (pin "1") (pinfunction "1_1") (pintype "passive"))
      (node (ref "R21") (pin "2") (pinfunction "2_2") (pintype "passive"))
      (node (ref "R22") (pin "1") (pinfunction "1_1") (pintype "passive"))
    )
    (net (code "43") (name "Net-(IC4-IN)") (class "Default")
      (node (ref "IC4") (pin "2") (pinfunction "IN_2") (pintype "input"))
      (node (ref "VR9") (pin "1") (pinfunction "C_1") (pintype "passive"))
    )
    (net (code "44") (name "Net-(KICK-PadA)") (class "Default")
      (node (ref "KICK") (pin "A") (pinfunction "A_A") (pintype "passive"))
      (node (ref "R29") (pin "2") (pinfunction "2_2") (pintype "passive"))
    )
    (net (code "45") (name "Net-(LED_BLAU-PadA)") (class "Default")
      (node (ref "LED_BLAU") (pin "A") (pinfunction "A_A") (pintype "passive"))
      (node (ref "R4") (pin "2") (pinfunction "2_2") (pintype "passive"))
    )
    (net (code "46") (name "Net-(OK1A-A)") (class "Default")
      (node (ref "OK1") (pin "1") (pinfunction "A_1") (pintype "passive"))
      (node (ref "R32") (pin "1") (pinfunction "1_1") (pintype "passive"))
    )
    (net (code "47") (name "Net-(OK1A-C)") (class "Default")
      (node (ref "OK1") (pin "2") (pinfunction "C_2") (pintype "passive"))
      (node (ref "OK1") (pin "3") (pinfunction "A_3") (pintype "passive"))
    )
    (net (code "48") (name "Net-(OK1A-COL)") (class "Default")
      (node (ref "OK1") (pin "8") (pinfunction "COL_8") (pintype "passive"))
      (node (ref "Q2") (pin "G") (pinfunction "G_G") (pintype "passive"))
      (node (ref "Q3") (pin "G") (pinfunction "G_G") (pintype "passive"))
      (node (ref "R34") (pin "2") (pinfunction "2_2") (pintype "passive"))
    )
    (net (code "49") (name "Net-(OK1A-EMIT)") (class "Default")
      (node (ref "OK1") (pin "7") (pinfunction "EMIT_7") (pintype "passive"))
      (node (ref "VR1") (pin "1") (pinfunction "C_1") (pintype "passive"))
    )
    (net (code "50") (name "Net-(OK1B-COL)") (class "Default")
      (node (ref "OK1") (pin "6") (pinfunction "COL_6") (pintype "passive"))
      (node (ref "Q4") (pin "G") (pinfunction "G_G") (pintype "passive"))
      (node (ref "Q5") (pin "G") (pinfunction "G_G") (pintype "passive"))
      (node (ref "R42") (pin "2") (pinfunction "2_2") (pintype "passive"))
    )
    (net (code "51") (name "Net-(OK1B-EMIT)") (class "Default")
      (node (ref "OK1") (pin "5") (pinfunction "EMIT_5") (pintype "passive"))
      (node (ref "VR3") (pin "1") (pinfunction "C_1") (pintype "passive"))
    )
    (net (code "52") (name "Net-(Q2-PadS)") (class "Default")
      (node (ref "Q2") (pin "S") (pinfunction "S_S") (pintype "passive"))
      (node (ref "Q3") (pin "S") (pinfunction "S_S") (pintype "passive"))
    )
    (net (code "53") (name "Net-(Q4-PadS)") (class "Default")
      (node (ref "Q4") (pin "S") (pinfunction "S_S") (pintype "passive"))
      (node (ref "Q5") (pin "S") (pinfunction "S_S") (pintype "passive"))
    )
    (net (code "54") (name "Net-(R6-Pad2)") (class "Default")
      (node (ref "R6") (pin "2") (pinfunction "2_2") (pintype "passive"))
      (node (ref "SJ1") (pin "2") (pinfunction "2_2") (pintype "passive"))
    )
    (net (code "55") (name "Net-(R7-Pad2)") (class "Default")
      (node (ref "R7") (pin "2") (pinfunction "2_2") (pintype "passive"))
      (node (ref "T4") (pin "B") (pinfunction "B_B") (pintype "passive"))
    )
    (net (code "56") (name "Net-(R26-Pad2)") (class "Default")
      (node (ref "R26") (pin "2") (pinfunction "2_2") (pintype "passive"))
      (node (ref "ROT") (pin "A") (pinfunction "A_A") (pintype "passive"))
    )
    (net (code "57") (name "Net-(RJ_1-PadP$4)") (class "Default")
      (node (ref "RJ_1") (pin "P$4") (pinfunction "P$4_P$4") (pintype "bidirectional"))
      (node (ref "RJ_2") (pin "P$4") (pinfunction "P$4_P$4") (pintype "bidirectional"))
      (node (ref "SJ2") (pin "2") (pinfunction "2_2") (pintype "passive"))
    )
    (net (code "58") (name "Net-(T1-B)") (class "Default")
      (node (ref "R5") (pin "2") (pinfunction "2_2") (pintype "passive"))
      (node (ref "T1") (pin "1") (pinfunction "B_1") (pintype "passive"))
    )
    (net (code "59") (name "Net-(T1-C)") (class "Default")
      (node (ref "T1") (pin "3") (pinfunction "C_3") (pintype "passive"))
      (node (ref "TDB-05") (pin "-") (pinfunction "2_-") (pintype "passive"))
    )
    (net (code "60") (name "Net-(T2-B)") (class "Default")
      (node (ref "R23") (pin "2") (pinfunction "2_2") (pintype "passive"))
      (node (ref "T2") (pin "1") (pinfunction "B_1") (pintype "passive"))
    )
    (net (code "61") (name "Net-(T3-B)") (class "Default")
      (node (ref "R1") (pin "2") (pinfunction "2_2") (pintype "passive"))
      (node (ref "T3") (pin "1") (pinfunction "B_1") (pintype "passive"))
    )
    (net (code "62") (name "Net-(T3-C)") (class "Default")
      (node (ref "LED_BLAU") (pin "C") (pinfunction "C_C") (pintype "passive"))
      (node (ref "R7") (pin "1") (pinfunction "1_1") (pintype "passive"))
      (node (ref "T3") (pin "3") (pinfunction "C_3") (pintype "passive"))
    )
    (net (code "63") (name "Net-(T5-B)") (class "Default")
      (node (ref "R16") (pin "2") (pinfunction "2_2") (pintype "passive"))
      (node (ref "T5") (pin "1") (pinfunction "B_1") (pintype "passive"))
    )
    (net (code "64") (name "Net-(T6-B)") (class "Default")
      (node (ref "R17") (pin "2") (pinfunction "2_2") (pintype "passive"))
      (node (ref "T6") (pin "1") (pinfunction "B_1") (pintype "passive"))
    )
    (net (code "65") (name "Net-(T7-B)") (class "Default")
      (node (ref "R15") (pin "2") (pinfunction "2_2") (pintype "passive"))
      (node (ref "T7") (pin "1") (pinfunction "B_1") (pintype "passive"))
    )
    (net (code "66") (name "Net-(U$1-RS)") (class "Default")
      (node (ref "R31") (pin "2") (pinfunction "2_2") (pintype "passive"))
      (node (ref "U$1") (pin "8") (pinfunction "RS_8") (pintype "input"))
    )
    (net (code "67") (name "Net-(U$2-AREF)") (class "Default")
      (node (ref "C14") (pin "2") (pinfunction "2_2") (pintype "passive"))
      (node (ref "U$2") (pin "21") (pinfunction "AREF_21") (pintype "bidirectional"))
    )
    (net (code "68") (name "Net-(U$2-PE1(XTAL1))") (class "Default")
      (node (ref "C11") (pin "2") (pinfunction "2_2") (pintype "passive"))
      (node (ref "Q1") (pin "1") (pinfunction "1_1") (pintype "passive"))
      (node (ref "U$2") (pin "10") (pinfunction "PE1(XTAL1)_10") (pintype "bidirectional"))
    )
    (net (code "69") (name "Net-(U$2-PE2(XTAL2))") (class "Default")
      (node (ref "C10") (pin "2") (pinfunction "2_2") (pintype "passive"))
      (node (ref "Q1") (pin "2") (pinfunction "2_2") (pintype "passive"))
      (node (ref "U$2") (pin "11") (pinfunction "PE2(XTAL2)_11") (pintype "bidirectional"))
    )
    (net (code "70") (name "Net-(U1-CB)") (class "Default")
      (node (ref "C4") (pin "1") (pinfunction "1_1") (pintype "passive"))
      (node (ref "U1") (pin "1") (pinfunction "CB_1") (pintype "input"))
    )
    (net (code "71") (name "Net-(U1-VIN)") (class "Default")
      (node (ref "C2") (pin "+") (pinfunction "+_+") (pintype "passive"))
      (node (ref "F1") (pin "2") (pinfunction "2_2") (pintype "passive"))
      (node (ref "U1") (pin "7") (pinfunction "VIN_7") (pintype "power_in"))
    )
    (net (code "72") (name "Net-(VR7-C)") (class "Default")
      (node (ref "IC11") (pin "IN") (pinfunction "IN_IN") (pintype "input"))
      (node (ref "VR7") (pin "1") (pinfunction "C_1") (pintype "passive"))
    )
    (net (code "73") (name "Net-(VR7-R)") (class "Default")
      (node (ref "R36") (pin "2") (pinfunction "2_2") (pintype "passive"))
      (node (ref "R37") (pin "1") (pinfunction "1_1") (pintype "passive"))
      (node (ref "VR7") (pin "2") (pinfunction "R_2") (pintype "passive"))
    )
    (net (code "74") (name "Net-(VR8-C)") (class "Default")
      (node (ref "IC12") (pin "IN") (pinfunction "IN_IN") (pintype "input"))
      (node (ref "VR8") (pin "1") (pinfunction "C_1") (pintype "passive"))
    )
    (net (code "75") (name "Net-(VR8-R)") (class "Default")
      (node (ref "R38") (pin "2") (pinfunction "2_2") (pintype "passive"))
      (node (ref "R39") (pin "1") (pinfunction "1_1") (pintype "passive"))
      (node (ref "VR8") (pin "2") (pinfunction "R_2") (pintype "passive"))
    )
    (net (code "76") (name "Net-(VR9-R)") (class "Default")
      (node (ref "R40") (pin "2") (pinfunction "2_2") (pintype "passive"))
      (node (ref "R41") (pin "1") (pinfunction "1_1") (pintype "passive"))
      (node (ref "VR9") (pin "2") (pinfunction "R_2") (pintype "passive"))
    )
    (net (code "77") (name "RST") (class "Default")
      (node (ref "ISP") (pin "5") (pinfunction "5_5") (pintype "passive"))
      (node (ref "U$2") (pin "31") (pinfunction "PE0(RESET)_31") (pintype "input"))
    )
    (net (code "78") (name "RXCAN") (class "Default")
      (node (ref "U$1") (pin "4") (pinfunction "RXD_4") (pintype "output"))
      (node (ref "U$2") (pin "7") (pinfunction "(RXCAN)PC3_7") (pintype "bidirectional"))
    )
    (net (code "79") (name "SPEAKER") (class "Default")
      (node (ref "R5") (pin "1") (pinfunction "1_1") (pintype "passive"))
      (node (ref "U$2") (pin "18") (pinfunction "PC5_18") (pintype "bidirectional"))
    )
    (net (code "80") (name "SW_1") (class "Default")
      (node (ref "SV4") (pin "8") (pinfunction "8_8") (pintype "passive"))
    )
    (net (code "81") (name "SW_1{slash}SCK_A") (class "Default")
      (node (ref "ISP") (pin "7") (pinfunction "7_7") (pintype "passive"))
      (node (ref "U$2") (pin "12") (pinfunction "(RXD)PD4_12") (pintype "bidirectional"))
    )
    (net (code "82") (name "SW_2") (class "Default")
      (node (ref "SV4") (pin "6") (pinfunction "6_6") (pintype "passive"))
    )
    (net (code "83") (name "SW_2{slash}MOSI_A") (class "Default")
      (node (ref "ISP") (pin "1") (pinfunction "1_1") (pintype "passive"))
      (node (ref "U$2") (pin "2") (pinfunction "(MOSI_A/TXD)PD3_2") (pintype "bidirectional"))
    )
    (net (code "84") (name "SW_3") (class "Default")
      (node (ref "SV4") (pin "4") (pinfunction "4_4") (pintype "passive"))
    )
    (net (code "85") (name "SW_3{slash}MISO_A") (class "Default")
      (node (ref "ISP") (pin "9") (pinfunction "9_9") (pintype "passive"))
      (node (ref "U$2") (pin "1") (pinfunction "(MISO_A)PD2_1") (pintype "bidirectional"))
    )
    (net (code "86") (name "SW_12V") (class "Default")
      (node (ref "OK1") (pin "4") (pinfunction "C_4") (pintype "passive"))
      (node (ref "SV2") (pin "4") (pinfunction "4_4") (pintype "passive"))
      (node (ref "U$2") (pin "15") (pinfunction "PD7_15") (pintype "bidirectional"))
    )
    (net (code "87") (name "SW_AKT") (class "Default")
      (node (ref "SJ3") (pin "1") (pinfunction "1_1") (pintype "passive"))
      (node (ref "SV2") (pin "6") (pinfunction "6_6") (pintype "passive"))
      (node (ref "U$2") (pin "8") (pinfunction "PB0_8") (pintype "bidirectional"))
      (node (ref "VR7") (pin "3") (pinfunction "A_3") (pintype "passive"))
    )
    (net (code "88") (name "SW_BLAU") (class "Default")
      (node (ref "SV2") (pin "10") (pinfunction "10_10") (pintype "passive"))
      (node (ref "U$2") (pin "3") (pinfunction "PC1_3") (pintype "bidirectional"))
    )
    (net (code "89") (name "SW_KICK") (class "Default")
      (node (ref "SJ3") (pin "2") (pinfunction "2_2") (pintype "passive"))
      (node (ref "SV4") (pin "10") (pinfunction "10_10") (pintype "passive"))
      (node (ref "U$2") (pin "25") (pinfunction "PC7_25") (pintype "bidirectional"))
      (node (ref "VR8") (pin "3") (pinfunction "A_3") (pintype "passive"))
    )
    (net (code "90") (name "SW_MOT") (class "Default")
      (node (ref "SV2") (pin "8") (pinfunction "8_8") (pintype "passive"))
      (node (ref "U$2") (pin "9") (pinfunction "PB1_9") (pintype "bidirectional"))
      (node (ref "VR9") (pin "3") (pinfunction "A_3") (pintype "passive"))
    )
    (net (code "91") (name "TXCAN") (class "Default")
      (node (ref "U$1") (pin "1") (pinfunction "TXD_1") (pintype "input"))
      (node (ref "U$2") (pin "6") (pinfunction "(TXCAN)PC2_6") (pintype "bidirectional"))
    )
    (net (code "92") (name "unconnected-(ISP-Pad3)") (class "Default")
      (node (ref "ISP") (pin "3") (pinfunction "3_3") (pintype "passive"))
    )
    (net (code "93") (name "unconnected-(U$1-VREF-Pad5)") (class "Default")
      (node (ref "U$1") (pin "5") (pinfunction "VREF_5") (pintype "output"))
    )
    (net (code "94") (name "unconnected-(U$2-PD1-Pad32)") (class "Default")
      (node (ref "U$2") (pin "32") (pinfunction "PD1_32") (pintype "bidirectional"))
    )
    (net (code "95") (name "unconnected-(U1-NC-Pad3)") (class "Default")
      (node (ref "U1") (pin "3") (pinfunction "NC_3") (pintype "no_connect"))
    )
    (net (code "96") (name "unconnected-(U1-NC_2-Pad2)") (class "Default")
      (node (ref "U1") (pin "2") (pinfunction "NC_2_2") (pintype "no_connect"))
    )
    (net (code "97") (name "unconnected-(U1-ON{slash}~{OFF}-Pad5)") (class "Default")
      (node (ref "U1") (pin "5") (pinfunction "ON/~{OFF}_5") (pintype "input"))
    )
  )
)
